# sensor_potensio.net
KiCad netlist of a schematic drawn in EAGLE
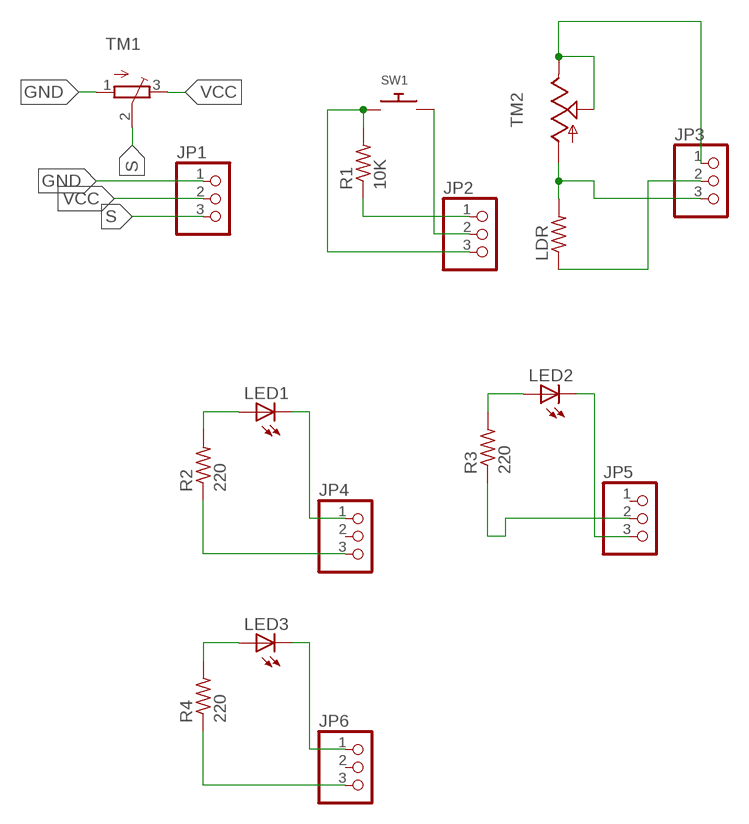
[diagram p0: schematic, sheet 1]

(export (version "E")
  (design (tool "Eeschema 10.0.6"))
  (components
    (comp (ref "JP1")
      (value "PINHD-1X3")
      (footprint "eagle-import:1X03")
      (libsource (lib "eagle-import") (part "PINHD-1X3"))
    )
    (comp (ref "JP2")
      (value "PINHD-1X3")
      (footprint "eagle-import:1X03")
      (libsource (lib "eagle-import") (part "PINHD-1X3"))
    )
    (comp (ref "JP3")
      (value "PINHD-1X3")
      (footprint "eagle-import:1X03")
      (libsource (lib "eagle-import") (part "PINHD-1X3"))
    )
    (comp (ref "JP4")
      (value "PINHD-1X3")
      (footprint "eagle-import:1X03")
      (libsource (lib "eagle-import") (part "PINHD-1X3"))
    )
    (comp (ref "JP5")
      (value "PINHD-1X3")
      (footprint "eagle-import:1X03")
      (libsource (lib "eagle-import") (part "PINHD-1X3"))
    )
    (comp (ref "JP6")
      (value "PINHD-1X3")
      (footprint "eagle-import:1X03")
      (libsource (lib "eagle-import") (part "PINHD-1X3"))
    )
    (comp (ref "LDR")
      (value "R-US_0204/5")
      (footprint "eagle-import:0204_5")
      (libsource (lib "eagle-import") (part "resistor_348_R-US_0204/5"))
    )
    (comp (ref "LED1")
      (value "LED5MM")
      (footprint "eagle-import:LED5MM")
      (libsource (lib "eagle-import") (part "LED5MM"))
    )
    (comp (ref "LED2")
      (value "LED5MM")
      (footprint "eagle-import:LED5MM")
      (libsource (lib "eagle-import") (part "LED5MM"))
    )
    (comp (ref "LED3")
      (value "LED5MM")
      (footprint "eagle-import:LED5MM")
      (libsource (lib "eagle-import") (part "LED5MM"))
    )
    (comp (ref "R1")
      (value "10K")
      (footprint "eagle-import:0207_7")
      (libsource (lib "eagle-import") (part "R-US_0207/7"))
    )
    (comp (ref "R2")
      (value "220")
      (footprint "eagle-import:0207_7")
      (libsource (lib "eagle-import") (part "R-US_0207/7"))
    )
    (comp (ref "R3")
      (value "220")
      (footprint "eagle-import:0207_7")
      (libsource (lib "eagle-import") (part "R-US_0207/7"))
    )
    (comp (ref "R4")
      (value "220")
      (footprint "eagle-import:0207_7")
      (libsource (lib "eagle-import") (part "R-US_0207/7"))
    )
    (comp (ref "SW1")
      (value "SWITCH_PUSHBUTTONEVQ-PE")
      (footprint "eagle-import:TACT_PANA-EVQ")
      (libsource (lib "eagle-import") (part "SWITCH_PUSHBUTTONEVQ-PE"))
    )
    (comp (ref "TM1")
      (value "TRIMPOT3386")
      (footprint "eagle-import:TRIM-3386")
      (libsource (lib "eagle-import") (part "TRIMPOT3386"))
    )
    (comp (ref "TM2")
      (value "TRIM")
      (footprint "eagle-import:6MM")
      (libsource (lib "eagle-import") (part "TRIM"))
    )
  )
  (nets
    (net (code "1") (name "GND") (class "Default")
      (node (ref "JP1") (pin "1") (pinfunction "1_1") (pintype "passive"))
      (node (ref "TM1") (pin "1") (pinfunction "A_1") (pintype "passive"))
    )
    (net (code "2") (name "Net-(JP2-Pad1)") (class "Default")
      (node (ref "JP2") (pin "1") (pinfunction "1_1") (pintype "passive"))
      (node (ref "R1") (pin "1") (pinfunction "1_1") (pintype "passive"))
    )
    (net (code "3") (name "Net-(JP2-Pad2)") (class "Default")
      (node (ref "JP2") (pin "2") (pinfunction "2_2") (pintype "passive"))
      (node (ref "SW1") (pin "P$2") (pinfunction "P$2_P$2") (pintype "passive"))
    )
    (net (code "4") (name "Net-(JP2-Pad3)") (class "Default")
      (node (ref "JP2") (pin "3") (pinfunction "3_3") (pintype "passive"))
      (node (ref "R1") (pin "2") (pinfunction "2_2") (pintype "passive"))
      (node (ref "SW1") (pin "P$1") (pinfunction "P$1_P$1") (pintype "passive"))
    )
    (net (code "5") (name "Net-(JP3-Pad1)") (class "Default")
      (node (ref "JP3") (pin "1") (pinfunction "1_1") (pintype "passive"))
      (node (ref "TM2") (pin "E") (pinfunction "E_E") (pintype "passive"))
      (node (ref "TM2") (pin "S") (pinfunction "S_S") (pintype "passive"))
    )
    (net (code "6") (name "Net-(JP3-Pad2)") (class "Default")
      (node (ref "JP3") (pin "2") (pinfunction "2_2") (pintype "passive"))
      (node (ref "LDR") (pin "1") (pinfunction "1_1") (pintype "passive"))
    )
    (net (code "7") (name "Net-(JP3-Pad3)") (class "Default")
      (node (ref "JP3") (pin "3") (pinfunction "3_3") (pintype "passive"))
      (node (ref "LDR") (pin "2") (pinfunction "2_2") (pintype "passive"))
      (node (ref "TM2") (pin "A") (pinfunction "A_A") (pintype "passive"))
    )
    (net (code "8") (name "Net-(JP4-Pad3)") (class "Default")
      (node (ref "JP4") (pin "3") (pinfunction "3_3") (pintype "passive"))
      (node (ref "R2") (pin "1") (pinfunction "1_1") (pintype "passive"))
    )
    (net (code "9") (name "Net-(JP5-Pad2)") (class "Default")
      (node (ref "JP5") (pin "2") (pinfunction "2_2") (pintype "passive"))
      (node (ref "R3") (pin "1") (pinfunction "1_1") (pintype "passive"))
    )
    (net (code "10") (name "Net-(JP6-Pad3)") (class "Default")
      (node (ref "JP6") (pin "3") (pinfunction "3_3") (pintype "passive"))
      (node (ref "R4") (pin "1") (pinfunction "1_1") (pintype "passive"))
    )
    (net (code "11") (name "Net-(LED1-C)") (class "Default")
      (node (ref "JP4") (pin "1") (pinfunction "1_1") (pintype "passive"))
      (node (ref "LED1") (pin "K") (pinfunction "C_K") (pintype "passive"))
    )
    (net (code "12") (name "Net-(LED1-PadA)") (class "Default")
      (node (ref "LED1") (pin "A") (pinfunction "A_A") (pintype "passive"))
      (node (ref "R2") (pin "2") (pinfunction "2_2") (pintype "passive"))
    )
    (net (code "13") (name "Net-(LED2-C)") (class "Default")
      (node (ref "JP5") (pin "3") (pinfunction "3_3") (pintype "passive"))
      (node (ref "LED2") (pin "K") (pinfunction "C_K") (pintype "passive"))
    )
    (net (code "14") (name "Net-(LED2-PadA)") (class "Default")
      (node (ref "LED2") (pin "A") (pinfunction "A_A") (pintype "passive"))
      (node (ref "R3") (pin "2") (pinfunction "2_2") (pintype "passive"))
    )
    (net (code "15") (name "Net-(LED3-C)") (class "Default")
      (node (ref "JP6") (pin "1") (pinfunction "1_1") (pintype "passive"))
      (node (ref "LED3") (pin "K") (pinfunction "C_K") (pintype "passive"))
    )
    (net (code "16") (name "Net-(LED3-PadA)") (class "Default")
      (node (ref "LED3") (pin "A") (pinfunction "A_A") (pintype "passive"))
      (node (ref "R4") (pin "2") (pinfunction "2_2") (pintype "passive"))
    )
    (net (code "17") (name "S") (class "Default")
      (node (ref "JP1") (pin "3") (pinfunction "3_3") (pintype "passive"))
      (node (ref "TM1") (pin "2") (pinfunction "S_2") (pintype "passive"))
    )
    (net (code "18") (name "VCC") (class "Default")
      (node (ref "JP1") (pin "2") (pinfunction "2_2") (pintype "passive"))
      (node (ref "TM1") (pin "3") (pinfunction "E_3") (pintype "passive"))
    )
    (net (code "19") (name "unconnected-(JP4-Pad2)") (class "Default")
      (node (ref "JP4") (pin "2") (pinfunction "2_2") (pintype "passive"))
    )
    (net (code "20") (name "unconnected-(JP5-Pad1)") (class "Default")
      (node (ref "JP5") (pin "1") (pinfunction "1_1") (pintype "passive"))
    )
    (net (code "21") (name "unconnected-(JP6-Pad2)") (class "Default")
      (node (ref "JP6") (pin "2") (pinfunction "2_2") (pintype "passive"))
    )
  )
)
